# EMCO_DC-DC.net
KiCad netlist of a schematic drawn in Altium Designer
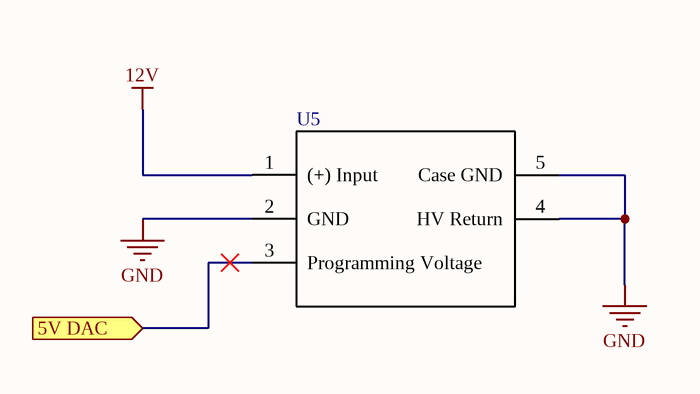
[diagram p0: EMCO DC-DC.SchDoc]

(export (version "E")
  (design (tool "Eeschema 10.0.6"))
  (components
    (comp (ref "U5")
      (value "C80")
      (footprint "C80")
      (description "DC DC CONVERTER 8000V 1W")
      (fields (field (name "MANUFACTURER") "XP Power") (field (name "DIGIKEY PART NUMBER") "1470-3260-ND"))
      (libsource (lib "Control_Board_Library") (part "C80"))
    )
  )
  (nets
    (net (code "1") (name "/5V DAC") (class "Default")
      (node (ref "U5") (pin "3") (pinfunction "Programming_Voltage_3") (pintype "passive"))
    )
    (net (code "2") (name "12V") (class "Default")
      (node (ref "U5") (pin "1") (pinfunction "(+)_Input_1") (pintype "passive"))
    )
    (net (code "3") (name "GND") (class "Default")
      (node (ref "U5") (pin "2") (pinfunction "GND_2") (pintype "passive"))
      (node (ref "U5") (pin "4") (pinfunction "HV_Return_4") (pintype "passive"))
      (node (ref "U5") (pin "5") (pinfunction "Case_GND_5") (pintype "passive"))
    )
  )
)
